# 3-LoadDrivers.net
KiCad netlist of a schematic drawn in Altium Designer
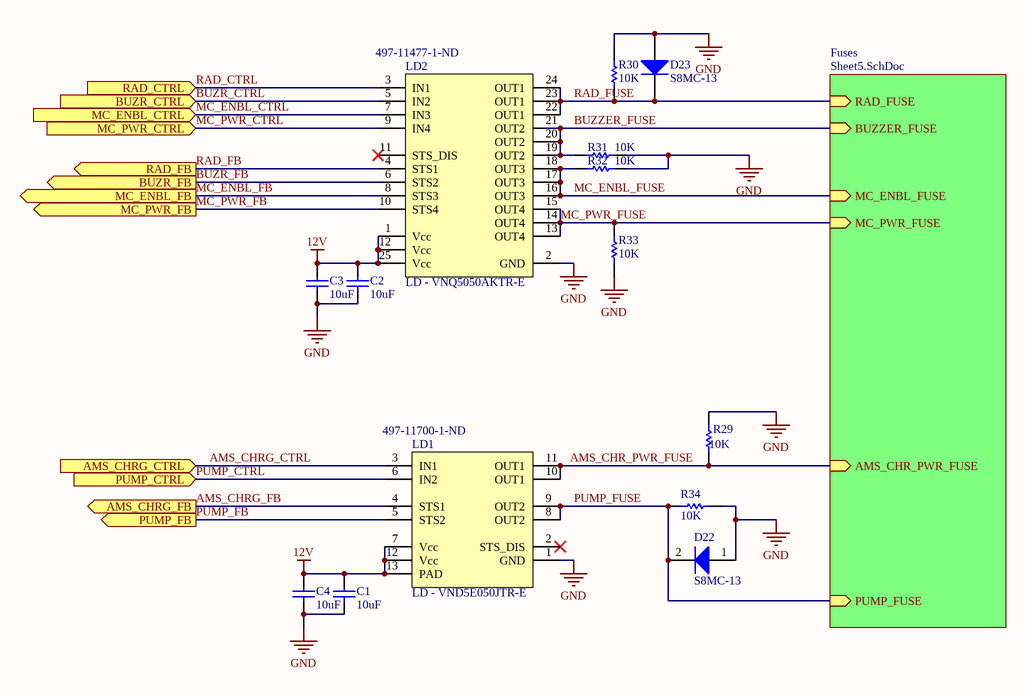
[diagram p0: 3-LoadDrivers.SchDoc]

(export (version "E")
  (design (tool "Eeschema 10.0.6"))
  (components
    (comp (ref "C1")
      (value "10uF")
      (footprint "1608[0603]")
      (description "Capacitor (Semiconductor SIM Model)")
      (fields (field (name "Comment") "Cap Semi") (field (name "PUBLISHER") "Altium Limited"))
      (libsource (lib "Miscellaneous Devices") (part "Cap Semi"))
    )
    (comp (ref "C2")
      (value "10uF")
      (footprint "1608[0603]")
      (description "Capacitor (Semiconductor SIM Model)")
      (fields (field (name "Comment") "Cap Semi") (field (name "PUBLISHER") "Altium Limited"))
      (libsource (lib "Miscellaneous Devices") (part "Cap Semi"))
    )
    (comp (ref "C3")
      (value "10uF")
      (footprint "1608[0603]")
      (description "Capacitor (Semiconductor SIM Model)")
      (fields (field (name "Comment") "Cap Semi") (field (name "PUBLISHER") "Altium Limited"))
      (libsource (lib "Miscellaneous Devices") (part "Cap Semi"))
    )
    (comp (ref "C4")
      (value "10uF")
      (footprint "1608[0603]")
      (description "Capacitor (Semiconductor SIM Model)")
      (fields (field (name "Comment") "Cap Semi") (field (name "PUBLISHER") "Altium Limited"))
      (libsource (lib "Miscellaneous Devices") (part "Cap Semi"))
    )
    (comp (ref "D22")
      (value "S8MC-13")
      (footprint "S8MC-13")
      (description "Default Diode")
      (libsource (lib "Miscellaneous Devices") (part "Diode"))
    )
    (comp (ref "D23")
      (value "S8MC-13")
      (footprint "S8MC-13")
      (description "Default Diode")
      (libsource (lib "") (part "Diode_1"))
    )
    (comp (ref "LD1")
      (value "LD - VND5E050JTR-E")
      (fields (field (name "SUPPLIER PART NUMBER 1") "497-11700-1-ND"))
      (libsource (lib "Power_PCB") (part "LOAD DRIVER - VND5E050JTR-E"))
    )
    (comp (ref "LD2")
      (value "LD - VNQ5050AKTR-E")
      (footprint "24-SOP (0.295\", 7.50mm Width) Exposed Pad")
      (fields (field (name "SUPPLIER PART NUMBER 1") "497-11477-1-ND"))
      (libsource (lib "FE Schem Lib") (part "LOAD DRIVER - VNQ5050"))
    )
    (comp (ref "R29")
      (value "10K")
      (footprint "RESC0603(1608)_L")
      (description "0603 (1608 Metric) Chip Resistor")
      (libsource (lib "Altium Content Vault") (part "CMP-1591-00001-1"))
    )
    (comp (ref "R30")
      (value "10K")
      (footprint "RESC0603(1608)_L")
      (description "0603 (1608 Metric) Chip Resistor")
      (libsource (lib "Altium Content Vault") (part "CMP-1591-00001-1"))
    )
    (comp (ref "R31")
      (value "10K")
      (footprint "RESC0603(1608)_L")
      (description "0603 (1608 Metric) Chip Resistor")
      (libsource (lib "Altium Content Vault") (part "RES_3"))
    )
    (comp (ref "R32")
      (value "10K")
      (footprint "RESC0603(1608)_L")
      (description "0603 (1608 Metric) Chip Resistor")
      (libsource (lib "Altium Content Vault") (part "CMP-1591-00001-1"))
    )
    (comp (ref "R33")
      (value "10K")
      (footprint "RESC0603(1608)_L")
      (description "0603 (1608 Metric) Chip Resistor")
      (libsource (lib "Altium Content Vault") (part "CMP-1591-00001-1"))
    )
    (comp (ref "R34")
      (value "10K")
      (footprint "RESC0603(1608)_L")
      (description "0603 (1608 Metric) Chip Resistor")
      (libsource (lib "Altium Content Vault") (part "CMP-1591-00001-1"))
    )
  )
  (nets
    (net (code "1") (name "/AMS_CHRG_CTRL") (class "Default")
      (node (ref "LD1") (pin "3") (pinfunction "IN1_3") (pintype "passive"))
    )
    (net (code "2") (name "/AMS_CHRG_FB") (class "Default")
      (node (ref "LD1") (pin "4") (pinfunction "STS1_4") (pintype "passive"))
    )
    (net (code "3") (name "/AMS_CHR_PWR_FUSE") (class "Default")
      (node (ref "LD1") (pin "10") (pinfunction "OUT1_10") (pintype "passive"))
      (node (ref "LD1") (pin "11") (pinfunction "OUT1_11") (pintype "passive"))
      (node (ref "R29") (pin "1") (pinfunction "1_1") (pintype "passive"))
    )
    (net (code "4") (name "/BUZR_CTRL") (class "Default")
      (node (ref "LD2") (pin "5") (pinfunction "IN2_5") (pintype "passive"))
    )
    (net (code "5") (name "/BUZR_FB") (class "Default")
      (node (ref "LD2") (pin "6") (pinfunction "STS2_6") (pintype "passive"))
    )
    (net (code "6") (name "/BUZZER_FUSE") (class "Default")
      (node (ref "LD2") (pin "19") (pinfunction "OUT2_19") (pintype "passive"))
      (node (ref "LD2") (pin "20") (pinfunction "OUT2_20") (pintype "passive"))
      (node (ref "LD2") (pin "21") (pinfunction "OUT2_21") (pintype "passive"))
      (node (ref "R31") (pin "1") (pinfunction "1_1") (pintype "passive"))
    )
    (net (code "7") (name "/MC_ENBL_CTRL") (class "Default")
      (node (ref "LD2") (pin "7") (pinfunction "IN3_7") (pintype "passive"))
    )
    (net (code "8") (name "/MC_ENBL_FB") (class "Default")
      (node (ref "LD2") (pin "8") (pinfunction "STS3_8") (pintype "passive"))
    )
    (net (code "9") (name "/MC_ENBL_FUSE") (class "Default")
      (node (ref "LD2") (pin "16") (pinfunction "OUT3_16") (pintype "passive"))
      (node (ref "LD2") (pin "17") (pinfunction "OUT3_17") (pintype "passive"))
      (node (ref "LD2") (pin "18") (pinfunction "OUT3_18") (pintype "passive"))
      (node (ref "R32") (pin "1") (pinfunction "1_1") (pintype "passive"))
    )
    (net (code "10") (name "/MC_PWR_CTRL") (class "Default")
      (node (ref "LD2") (pin "9") (pinfunction "IN4_9") (pintype "passive"))
    )
    (net (code "11") (name "/MC_PWR_FB") (class "Default")
      (node (ref "LD2") (pin "10") (pinfunction "STS4_10") (pintype "passive"))
    )
    (net (code "12") (name "/MC_PWR_FUSE") (class "Default")
      (node (ref "LD2") (pin "13") (pinfunction "OUT4_13") (pintype "passive"))
      (node (ref "LD2") (pin "14") (pinfunction "OUT4_14") (pintype "passive"))
      (node (ref "LD2") (pin "15") (pinfunction "OUT4_15") (pintype "passive"))
      (node (ref "R33") (pin "2") (pinfunction "2_2") (pintype "passive"))
    )
    (net (code "13") (name "/PUMP_CTRL") (class "Default")
      (node (ref "LD1") (pin "6") (pinfunction "IN2_6") (pintype "passive"))
    )
    (net (code "14") (name "/PUMP_FB") (class "Default")
      (node (ref "LD1") (pin "5") (pinfunction "STS2_5") (pintype "passive"))
    )
    (net (code "15") (name "/PUMP_FUSE") (class "Default")
      (node (ref "D22") (pin "2") (pinfunction "K_2") (pintype "passive"))
      (node (ref "LD1") (pin "8") (pinfunction "OUT2_8") (pintype "passive"))
      (node (ref "LD1") (pin "9") (pinfunction "OUT2_9") (pintype "passive"))
      (node (ref "R34") (pin "2") (pinfunction "2_2") (pintype "passive"))
    )
    (net (code "16") (name "/RAD_CTRL") (class "Default")
      (node (ref "LD2") (pin "3") (pinfunction "IN1_3") (pintype "passive"))
    )
    (net (code "17") (name "/RAD_FB") (class "Default")
      (node (ref "LD2") (pin "4") (pinfunction "STS1_4") (pintype "passive"))
    )
    (net (code "18") (name "/RAD_FUSE") (class "Default")
      (node (ref "D23") (pin "2") (pinfunction "K_2") (pintype "passive"))
      (node (ref "LD2") (pin "22") (pinfunction "OUT1_22") (pintype "passive"))
      (node (ref "LD2") (pin "23") (pinfunction "OUT1_23") (pintype "passive"))
      (node (ref "LD2") (pin "24") (pinfunction "OUT1_24") (pintype "passive"))
      (node (ref "R30") (pin "1") (pinfunction "1_1") (pintype "passive"))
    )
    (net (code "19") (name "12V") (class "Default")
      (node (ref "C1") (pin "2") (pinfunction "2_2") (pintype "passive"))
      (node (ref "C2") (pin "2") (pinfunction "2_2") (pintype "passive"))
      (node (ref "C3") (pin "2") (pinfunction "2_2") (pintype "passive"))
      (node (ref "C4") (pin "2") (pinfunction "2_2") (pintype "passive"))
      (node (ref "LD1") (pin "12") (pinfunction "Vcc_12") (pintype "passive"))
      (node (ref "LD1") (pin "13") (pinfunction "PAD_13") (pintype "passive"))
      (node (ref "LD1") (pin "7") (pinfunction "Vcc_7") (pintype "passive"))
      (node (ref "LD2") (pin "1") (pinfunction "Vcc_1") (pintype "passive"))
      (node (ref "LD2") (pin "12") (pinfunction "Vcc_12") (pintype "passive"))
      (node (ref "LD2") (pin "25") (pinfunction "Vcc_25") (pintype "passive"))
    )
    (net (code "20") (name "GND") (class "Default")
      (node (ref "C1") (pin "1") (pinfunction "1_1") (pintype "passive"))
      (node (ref "C2") (pin "1") (pinfunction "1_1") (pintype "passive"))
      (node (ref "C3") (pin "1") (pinfunction "1_1") (pintype "passive"))
      (node (ref "C4") (pin "1") (pinfunction "1_1") (pintype "passive"))
      (node (ref "D22") (pin "1") (pinfunction "A_1") (pintype "passive"))
      (node (ref "D23") (pin "1") (pinfunction "A_1") (pintype "passive"))
      (node (ref "LD1") (pin "1") (pinfunction "GND_1") (pintype "passive"))
      (node (ref "LD2") (pin "2") (pinfunction "GND_2") (pintype "passive"))
      (node (ref "R29") (pin "2") (pinfunction "2_2") (pintype "passive"))
      (node (ref "R30") (pin "2") (pinfunction "2_2") (pintype "passive"))
      (node (ref "R31") (pin "2") (pinfunction "2_2") (pintype "passive"))
      (node (ref "R32") (pin "2") (pinfunction "2_2") (pintype "passive"))
      (node (ref "R33") (pin "1") (pinfunction "1_1") (pintype "passive"))
      (node (ref "R34") (pin "1") (pinfunction "1_1") (pintype "passive"))
    )
    (net (code "21") (name "unconnected-(LD1-STS_DIS-Pad2)") (class "Default")
      (node (ref "LD1") (pin "2") (pinfunction "STS_DIS_2") (pintype "passive+no_connect"))
    )
    (net (code "22") (name "unconnected-(LD2-STS_DIS-Pad11)") (class "Default")
      (node (ref "LD2") (pin "11") (pinfunction "STS_DIS_11") (pintype "passive+no_connect"))
    )
  )
)
